# Throughhole_final_schematic.net
KiCad netlist of a schematic drawn in Altium Designer
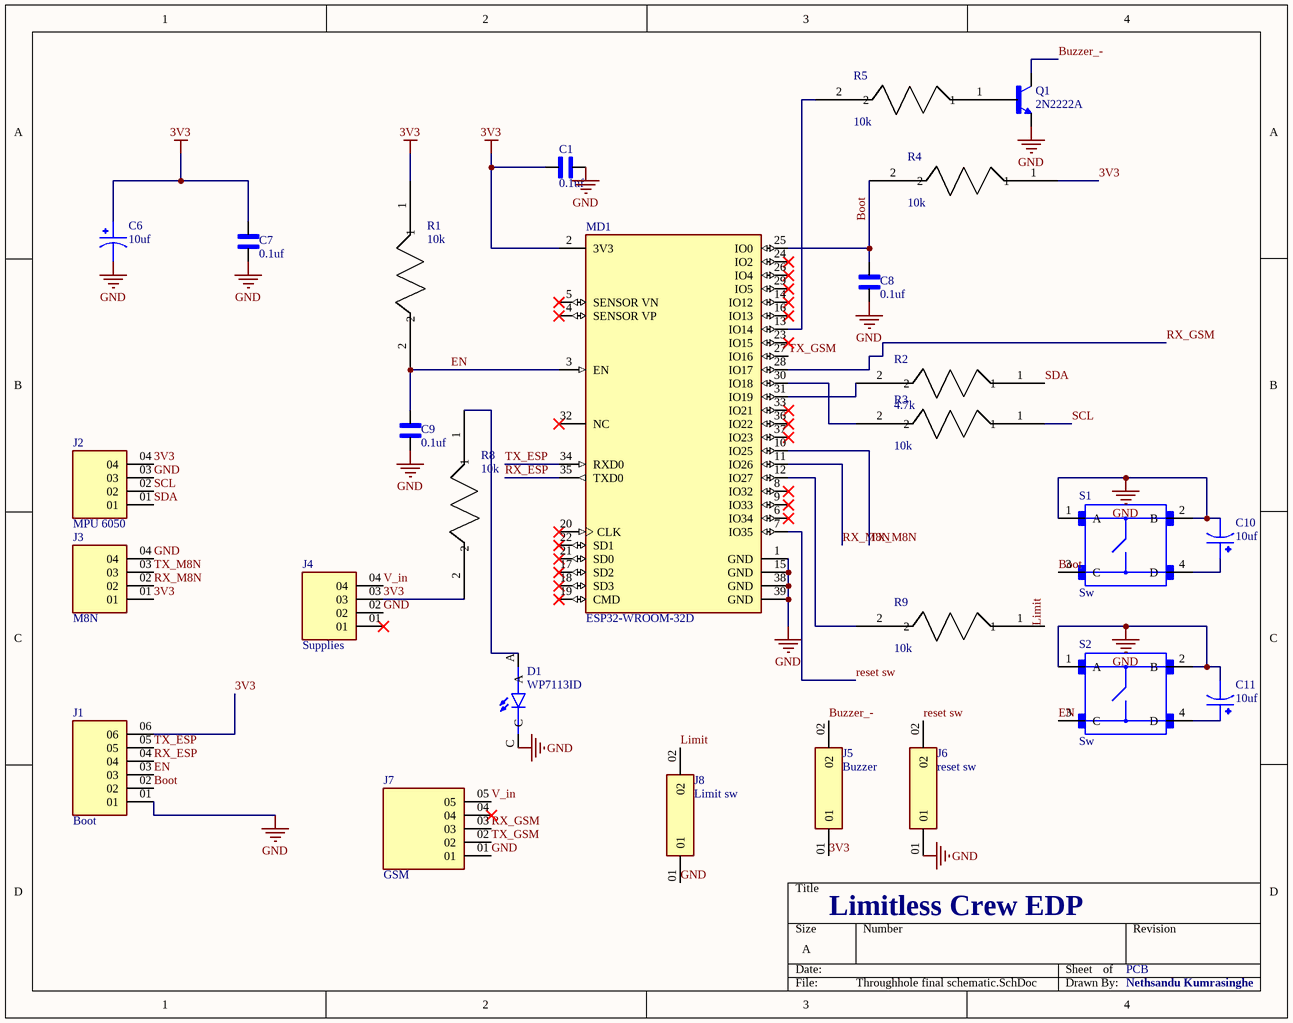
[diagram p0: Throughhole final schematic.SchDoc]

(export (version "E")
  (design (tool "Eeschema 10.0.6"))
  (components
    (comp (ref "C1")
      (value "0.1uf")
      (footprint "CAPRB500W50L450T250H550")
      (description "CAP CER 0.1UF 100V X7R RADIAL")
      (fields (field (name "MF") "TDK") (field (name "MP") "FK24X7R2A104KN000"))
      (libsource (lib "") (part "0.1uf_1"))
    )
    (comp (ref "C6")
      (value "10uf")
      (footprint "CAPPRD500W60D1000H2200")
      (description "CAP ALUM 10UF 20% 350V RADIAL")
      (fields (field (name "MF") "EPCOS") (field (name "MP") "B43890A4106M000"))
      (libsource (lib "") (part "10uf_1"))
    )
    (comp (ref "C7")
      (value "0.1uf")
      (footprint "CAPRB500W50L450T250H550")
      (description "CAP CER 0.1UF 100V X7R RADIAL")
      (fields (field (name "MF") "TDK") (field (name "MP") "FK24X7R2A104KN000"))
      (libsource (lib "") (part "0.1uf_2"))
    )
    (comp (ref "C8")
      (value "0.1uf")
      (footprint "CAPRB500W50L450T250H550")
      (description "CAP CER 0.1UF 100V X7R RADIAL")
      (fields (field (name "MF") "TDK") (field (name "MP") "FK24X7R2A104KN000"))
      (libsource (lib "Integrated_Library_final") (part "0.1uf"))
    )
    (comp (ref "C9")
      (value "0.1uf")
      (footprint "CAPRB500W50L450T250H550")
      (description "CAP CER 0.1UF 100V X7R RADIAL")
      (fields (field (name "MF") "TDK") (field (name "MP") "FK24X7R2A104KN000"))
      (libsource (lib "") (part "0.1uf_2"))
    )
    (comp (ref "C10")
      (value "10uf")
      (footprint "CAPPRD500W60D1000H2200")
      (description "CAP ALUM 10UF 20% 350V RADIAL")
      (fields (field (name "MF") "EPCOS") (field (name "MP") "B43890A4106M000"))
      (libsource (lib "Integrated_Library_final") (part "10uf"))
    )
    (comp (ref "C11")
      (value "10uf")
      (footprint "CAPPRD500W60D1000H2200")
      (description "CAP ALUM 10UF 20% 350V RADIAL")
      (fields (field (name "MF") "EPCOS") (field (name "MP") "B43890A4106M000"))
      (libsource (lib "Integrated_Library_final") (part "10uf"))
    )
    (comp (ref "D1")
      (value "WP7113ID")
      (footprint "LED_WP7113ID")
      (description "Red 617nm LED Indication - Discrete 2V Radial")
      (fields (field (name "MF") "Kingbright"))
      (libsource (lib "WP7113ID") (part "WP7113ID"))
    )
    (comp (ref "J1")
      (value "Boot")
      (footprint "SAMTEC_HMTSW-106-X-X-S-X")
      (description ".100 High-Temp Variable Post Height Terminal Strip")
      (fields (field (name "MF") "SAMTEC") (field (name "MP") "HMTSW-106-07-T-S-200"))
      (libsource (lib "Integrated_Library_final") (part "connector"))
    )
    (comp (ref "J2")
      (value "MPU 6050")
      (footprint "SAMTEC_MTLW-104-X-X-S-X")
      (fields (field (name "MF") "{'manufacturer': u'Samtec Inc.'}") (field (name "MP") "MTLW-104-X-X-S-X"))
      (libsource (lib "MTLW-104-X-X-S-X") (part "MTLW-104-X-X-S-X"))
    )
    (comp (ref "J3")
      (value "M8N")
      (footprint "SAMTEC_MTLW-104-X-X-S-X")
      (fields (field (name "MF") "{'manufacturer': u'Samtec Inc.'}") (field (name "MP") "MTLW-104-X-X-S-X"))
      (libsource (lib "MTLW-104-X-X-S-X") (part "MTLW-104-X-X-S-X"))
    )
    (comp (ref "J4")
      (value "Supplies")
      (footprint "SAMTEC_MTLW-104-X-X-S-X")
      (fields (field (name "MF") "{'manufacturer': u'Samtec Inc.'}") (field (name "MP") "MTLW-104-X-X-S-X"))
      (libsource (lib "MTLW-104-X-X-S-X") (part "MTLW-104-X-X-S-X"))
    )
    (comp (ref "J5")
      (value "Buzzer")
      (footprint "SAMTEC_MTSW-101-X-X-D-X")
      (description "Variable Height PCB Header Strips, 0.100 pitch")
      (fields (field (name "MF") "SAMTEC") (field (name "MP") "MTSW-101-09-L-D-210"))
      (libsource (lib "MTSW-101-X-X-D-X") (part "MTSW-101-X-X-D-X"))
    )
    (comp (ref "J6")
      (value "reset sw")
      (footprint "SAMTEC_MTSW-101-X-X-D-X")
      (description "Variable Height PCB Header Strips, 0.100 pitch")
      (fields (field (name "MF") "SAMTEC") (field (name "MP") "MTSW-101-09-L-D-210"))
      (libsource (lib "MTSW-101-X-X-D-X") (part "MTSW-101-X-X-D-X"))
    )
    (comp (ref "J7")
      (value "GSM")
      (footprint "SAMTEC_MTLW-105-06-T-S-135")
      (fields (field (name "MP") "MTLW-105-06-T-S-135"))
      (libsource (lib "MTLW-105-06-T-S-135") (part "MTLW-105-06-T-S-135"))
    )
    (comp (ref "J8")
      (value "Limit sw")
      (footprint "SAMTEC_MTSW-101-X-X-D-X")
      (description "Variable Height PCB Header Strips, 0.100 pitch")
      (fields (field (name "MF") "SAMTEC") (field (name "MP") "MTSW-101-09-L-D-210"))
      (libsource (lib "MTSW-101-X-X-D-X") (part "MTSW-101-X-X-D-X"))
    )
    (comp (ref "MD1")
      (value "ESP32-WROOM-32D")
      (footprint "FP-ESP32-WROOM-32D-MFG")
      (description "WIFI MODULE 32MBITS SPI FLASH")
      (fields
        (field (name "OCTOPART") "https://octopart.com/esp32-wroom-32d-espressif+systems-91040050")
        (field (name "MANUFACTURER") "Espressif Systems")
      )
      (libsource (lib "Integrated_Library_final") (part "esp32wroom32d"))
    )
    (comp (ref "Q1")
      (value "2N2222A")
      (footprint "TO92254P470H750-3")
      (description "BJT, TO-92, 40V, 600mA, NPN, 0.625W, 150Â°C")
      (fields (field (name "MF") "Diotec Semiconductor"))
      (libsource (lib "2N2222A") (part "2N2222A"))
    )
    (comp (ref "R1")
      (value "10k")
      (footprint "RESAD1100W55L680D260")
      (description "Fixed Resistor, Carbon Film, 0.25W, 10000ohm, 250V, 5% +/-Tol, -500,350ppm/Cel, Through Hole Mount")
      (fields
        (field (name "MANUFACTURER") "Yageo")
        (field (name "MANUFACTURER PART NUMBER") "CFR-25JR-52-10K")
      )
      (libsource (lib "Integrated_Library_final") (part "10k"))
    )
    (comp (ref "R2")
      (value "4.7k")
      (footprint "RESAD1100W55L680D260")
      (description "Fixed Resistor, Carbon Film, 0.25W, 4700ohm, 250V, 5% +/-Tol, -500,350ppm/Cel, Through Hole Mount")
      (fields
        (field (name "MANUFACTURER") "Yageo")
        (field (name "MANUFACTURER PART NUMBER") "CFR-25JR-52-4K7")
      )
      (libsource (lib "Integrated_Library_final") (part "4.7k"))
    )
    (comp (ref "R3")
      (value "10k")
      (footprint "RESAD1100W55L680D260")
      (description "Fixed Resistor, Carbon Film, 0.25W, 10000ohm, 250V, 5% +/-Tol, -500,350ppm/Cel, Through Hole Mount")
      (fields
        (field (name "MANUFACTURER") "Yageo")
        (field (name "MANUFACTURER PART NUMBER") "CFR-25JR-52-10K")
      )
      (libsource (lib "Integrated_Library_final") (part "10k"))
    )
    (comp (ref "R4")
      (value "10k")
      (footprint "RESAD1100W55L680D260")
      (description "Fixed Resistor, Carbon Film, 0.25W, 10000ohm, 250V, 5% +/-Tol, -500,350ppm/Cel, Through Hole Mount")
      (fields
        (field (name "MANUFACTURER") "Yageo")
        (field (name "MANUFACTURER PART NUMBER") "CFR-25JR-52-10K")
      )
      (libsource (lib "Integrated_Library_final") (part "10k"))
    )
    (comp (ref "R5")
      (value "10k")
      (footprint "RESAD1100W55L680D260")
      (description "Fixed Resistor, Carbon Film, 0.25W, 10000ohm, 250V, 5% +/-Tol, -500,350ppm/Cel, Through Hole Mount")
      (fields
        (field (name "MANUFACTURER") "Yageo")
        (field (name "MANUFACTURER PART NUMBER") "CFR-25JR-52-10K")
      )
      (libsource (lib "Integrated_Library_final") (part "10k"))
    )
    (comp (ref "R8")
      (value "10k")
      (footprint "RESAD1100W55L680D260")
      (description "Fixed Resistor, Carbon Film, 0.25W, 10000ohm, 250V, 5% +/-Tol, -500,350ppm/Cel, Through Hole Mount")
      (fields
        (field (name "MANUFACTURER") "Yageo")
        (field (name "MANUFACTURER PART NUMBER") "CFR-25JR-52-10K")
      )
      (libsource (lib "Integrated_Library_final") (part "10k"))
    )
    (comp (ref "R9")
      (value "10k")
      (footprint "RESAD1100W55L680D260")
      (description "Fixed Resistor, Carbon Film, 0.25W, 10000ohm, 250V, 5% +/-Tol, -500,350ppm/Cel, Through Hole Mount")
      (fields
        (field (name "MANUFACTURER") "Yageo")
        (field (name "MANUFACTURER PART NUMBER") "CFR-25JR-52-10K")
      )
      (libsource (lib "Integrated_Library_final") (part "10k"))
    )
    (comp (ref "S1")
      (value "Sw")
      (footprint "SW_TS-1109")
      (description "Heat Sink Full Brick DC/DC Converter Aluminum Top Mount")
      (fields (field (name "MP") "TS-1109") (field (name "MF") "Samtec Inc."))
      (libsource (lib "Integrated_Library_final") (part "Sw"))
    )
    (comp (ref "S2")
      (value "Sw")
      (footprint "SW_TS-1109")
      (description "Heat Sink Full Brick DC/DC Converter Aluminum Top Mount")
      (fields (field (name "MP") "TS-1109") (field (name "MF") "Samtec Inc."))
      (libsource (lib "Integrated_Library_final") (part "Sw"))
    )
  )
  (nets
    (net (code "1") (name "/Boot") (class "Default")
      (node (ref "C8") (pin "1") (pinfunction "1_1") (pintype "passive"))
      (node (ref "J1") (pin "02") (pinfunction "02_02") (pintype "passive"))
      (node (ref "MD1") (pin "25") (pinfunction "IO0_25") (pintype "bidirectional"))
      (node (ref "R4") (pin "2") (pinfunction "2_2") (pintype "passive"))
      (node (ref "S1") (pin "3") (pinfunction "C_3") (pintype "passive"))
    )
    (net (code "2") (name "/Buzzer_-") (class "Default")
      (node (ref "J5") (pin "02") (pinfunction "02_02") (pintype "passive"))
      (node (ref "Q1") (pin "3") (pinfunction "C_3") (pintype "passive"))
    )
    (net (code "3") (name "/EN") (class "Default")
      (node (ref "C9") (pin "2") (pinfunction "2_2") (pintype "passive"))
      (node (ref "J1") (pin "03") (pinfunction "03_03") (pintype "passive"))
      (node (ref "MD1") (pin "3") (pinfunction "EN_3") (pintype "input"))
      (node (ref "R1") (pin "2") (pinfunction "2_2") (pintype "passive"))
      (node (ref "S2") (pin "3") (pinfunction "C_3") (pintype "passive"))
    )
    (net (code "4") (name "/Limit") (class "Default")
      (node (ref "J8") (pin "02") (pinfunction "02_02") (pintype "passive"))
      (node (ref "R9") (pin "1") (pinfunction "1_1") (pintype "passive"))
    )
    (net (code "5") (name "/RX_ESP") (class "Default")
      (node (ref "J1") (pin "04") (pinfunction "04_04") (pintype "passive"))
      (node (ref "MD1") (pin "35") (pinfunction "TXD0_35") (pintype "output"))
    )
    (net (code "6") (name "/RX_GSM") (class "Default")
      (node (ref "J7") (pin "03") (pinfunction "03_03") (pintype "passive"))
      (node (ref "MD1") (pin "28") (pinfunction "IO17_28") (pintype "bidirectional"))
    )
    (net (code "7") (name "/RX_M8N") (class "Default")
      (node (ref "J3") (pin "02") (pinfunction "02_02") (pintype "passive"))
      (node (ref "MD1") (pin "11") (pinfunction "IO26_11") (pintype "bidirectional"))
    )
    (net (code "8") (name "/SCL") (class "Default")
      (node (ref "J2") (pin "02") (pinfunction "02_02") (pintype "passive"))
      (node (ref "R3") (pin "1") (pinfunction "1_1") (pintype "passive"))
    )
    (net (code "9") (name "/SDA") (class "Default")
      (node (ref "J2") (pin "01") (pinfunction "01_01") (pintype "passive"))
      (node (ref "R2") (pin "1") (pinfunction "1_1") (pintype "passive"))
    )
    (net (code "10") (name "/TX_ESP") (class "Default")
      (node (ref "J1") (pin "05") (pinfunction "05_05") (pintype "passive"))
      (node (ref "MD1") (pin "34") (pinfunction "RXD0_34") (pintype "input"))
    )
    (net (code "11") (name "/TX_GSM") (class "Default")
      (node (ref "J7") (pin "02") (pinfunction "02_02") (pintype "passive"))
      (node (ref "MD1") (pin "27") (pinfunction "IO16_27") (pintype "bidirectional"))
    )
    (net (code "12") (name "/TX_M8N") (class "Default")
      (node (ref "J3") (pin "03") (pinfunction "03_03") (pintype "passive"))
      (node (ref "MD1") (pin "10") (pinfunction "IO25_10") (pintype "bidirectional"))
    )
    (net (code "13") (name "/V_in") (class "Default")
      (node (ref "J4") (pin "04") (pinfunction "04_04") (pintype "passive"))
      (node (ref "J7") (pin "05") (pinfunction "05_05") (pintype "passive"))
    )
    (net (code "14") (name "/reset sw") (class "Default")
      (node (ref "J6") (pin "02") (pinfunction "02_02") (pintype "passive"))
      (node (ref "MD1") (pin "7") (pinfunction "IO35_7") (pintype "bidirectional"))
    )
    (net (code "15") (name "3V3") (class "Default")
      (node (ref "C1") (pin "1") (pinfunction "1_1") (pintype "passive"))
      (node (ref "C6") (pin "1") (pinfunction "1_1") (pintype "passive"))
      (node (ref "C7") (pin "2") (pinfunction "2_2") (pintype "passive"))
      (node (ref "J1") (pin "06") (pinfunction "06_06") (pintype "passive"))
      (node (ref "J2") (pin "04") (pinfunction "04_04") (pintype "passive"))
      (node (ref "J3") (pin "01") (pinfunction "01_01") (pintype "passive"))
      (node (ref "J4") (pin "03") (pinfunction "03_03") (pintype "passive"))
      (node (ref "J5") (pin "01") (pinfunction "01_01") (pintype "passive"))
      (node (ref "MD1") (pin "2") (pinfunction "3V3_2") (pintype "power_in"))
      (node (ref "R1") (pin "1") (pinfunction "1_1") (pintype "passive"))
      (node (ref "R4") (pin "1") (pinfunction "1_1") (pintype "passive"))
      (node (ref "R8") (pin "2") (pinfunction "2_2") (pintype "passive"))
    )
    (net (code "16") (name "GND") (class "Default")
      (node (ref "C1") (pin "2") (pinfunction "2_2") (pintype "passive"))
      (node (ref "C10") (pin "2") (pinfunction "2_2") (pintype "passive"))
      (node (ref "C11") (pin "2") (pinfunction "2_2") (pintype "passive"))
      (node (ref "C6") (pin "2") (pinfunction "2_2") (pintype "passive"))
      (node (ref "C7") (pin "1") (pinfunction "1_1") (pintype "passive"))
      (node (ref "C8") (pin "2") (pinfunction "2_2") (pintype "passive"))
      (node (ref "C9") (pin "1") (pinfunction "1_1") (pintype "passive"))
      (node (ref "D1") (pin "C") (pinfunction "C_C") (pintype "passive"))
      (node (ref "J1") (pin "01") (pinfunction "01_01") (pintype "passive"))
      (node (ref "J2") (pin "03") (pinfunction "03_03") (pintype "passive"))
      (node (ref "J3") (pin "04") (pinfunction "04_04") (pintype "passive"))
      (node (ref "J4") (pin "02") (pinfunction "02_02") (pintype "passive"))
      (node (ref "J6") (pin "01") (pinfunction "01_01") (pintype "passive"))
      (node (ref "J7") (pin "01") (pinfunction "01_01") (pintype "passive"))
      (node (ref "J8") (pin "01") (pinfunction "01_01") (pintype "passive"))
      (node (ref "MD1") (pin "1") (pinfunction "GND_1") (pintype "power_in"))
      (node (ref "MD1") (pin "15") (pinfunction "GND_15") (pintype "power_in"))
      (node (ref "MD1") (pin "38") (pinfunction "GND_38") (pintype "power_in"))
      (node (ref "MD1") (pin "39") (pinfunction "GND_39") (pintype "power_in"))
      (node (ref "Q1") (pin "1") (pinfunction "E_1") (pintype "passive"))
      (node (ref "S1") (pin "1") (pinfunction "A_1") (pintype "passive"))
      (node (ref "S1") (pin "2") (pinfunction "B_2") (pintype "passive"))
      (node (ref "S2") (pin "1") (pinfunction "A_1") (pintype "passive"))
      (node (ref "S2") (pin "2") (pinfunction "B_2") (pintype "passive"))
    )
    (net (code "17") (name "Net-(D1-PadA)") (class "Default")
      (node (ref "D1") (pin "A") (pinfunction "A_A") (pintype "passive"))
      (node (ref "R8") (pin "1") (pinfunction "1_1") (pintype "passive"))
    )
    (net (code "18") (name "Net-(MD1-IO14)") (class "Default")
      (node (ref "MD1") (pin "13") (pinfunction "IO14_13") (pintype "bidirectional"))
      (node (ref "R5") (pin "2") (pinfunction "2_2") (pintype "passive"))
    )
    (net (code "19") (name "Net-(MD1-IO18)") (class "Default")
      (node (ref "MD1") (pin "30") (pinfunction "IO18_30") (pintype "bidirectional"))
      (node (ref "R3") (pin "2") (pinfunction "2_2") (pintype "passive"))
    )
    (net (code "20") (name "Net-(MD1-IO19)") (class "Default")
      (node (ref "MD1") (pin "31") (pinfunction "IO19_31") (pintype "bidirectional"))
      (node (ref "R2") (pin "2") (pinfunction "2_2") (pintype "passive"))
    )
    (net (code "21") (name "Net-(MD1-IO27)") (class "Default")
      (node (ref "MD1") (pin "12") (pinfunction "IO27_12") (pintype "bidirectional"))
      (node (ref "R9") (pin "2") (pinfunction "2_2") (pintype "passive"))
    )
    (net (code "22") (name "Net-(Q1-B)") (class "Default")
      (node (ref "Q1") (pin "2") (pinfunction "B_2") (pintype "passive"))
      (node (ref "R5") (pin "1") (pinfunction "1_1") (pintype "passive"))
    )
    (net (code "23") (name "Net-(S1-D)") (class "Default")
      (node (ref "C10") (pin "1") (pinfunction "1_1") (pintype "passive"))
      (node (ref "S1") (pin "4") (pinfunction "D_4") (pintype "passive"))
    )
    (net (code "24") (name "Net-(S2-D)") (class "Default")
      (node (ref "C11") (pin "1") (pinfunction "1_1") (pintype "passive"))
      (node (ref "S2") (pin "4") (pinfunction "D_4") (pintype "passive"))
    )
    (net (code "25") (name "unconnected-(J4-Pad01)") (class "Default")
      (node (ref "J4") (pin "01") (pinfunction "01_01") (pintype "passive+no_connect"))
    )
    (net (code "26") (name "unconnected-(J7-Pad04)") (class "Default")
      (node (ref "J7") (pin "04") (pinfunction "04_04") (pintype "passive+no_connect"))
    )
    (net (code "27") (name "unconnected-(MD1-CLK-Pad20)") (class "Default")
      (node (ref "MD1") (pin "20") (pinfunction "CLK_20") (pintype "input+no_connect"))
    )
    (net (code "28") (name "unconnected-(MD1-CMD-Pad19)") (class "Default")
      (node (ref "MD1") (pin "19") (pinfunction "CMD_19") (pintype "bidirectional+no_connect"))
    )
    (net (code "29") (name "unconnected-(MD1-IO2-Pad24)") (class "Default")
      (node (ref "MD1") (pin "24") (pinfunction "IO2_24") (pintype "bidirectional+no_connect"))
    )
    (net (code "30") (name "unconnected-(MD1-IO4-Pad26)") (class "Default")
      (node (ref "MD1") (pin "26") (pinfunction "IO4_26") (pintype "bidirectional+no_connect"))
    )
    (net (code "31") (name "unconnected-(MD1-IO5-Pad29)") (class "Default")
      (node (ref "MD1") (pin "29") (pinfunction "IO5_29") (pintype "bidirectional+no_connect"))
    )
    (net (code "32") (name "unconnected-(MD1-IO12-Pad14)") (class "Default")
      (node (ref "MD1") (pin "14") (pinfunction "IO12_14") (pintype "bidirectional+no_connect"))
    )
    (net (code "33") (name "unconnected-(MD1-IO13-Pad16)") (class "Default")
      (node (ref "MD1") (pin "16") (pinfunction "IO13_16") (pintype "bidirectional+no_connect"))
    )
    (net (code "34") (name "unconnected-(MD1-IO15-Pad23)") (class "Default")
      (node (ref "MD1") (pin "23") (pinfunction "IO15_23") (pintype "bidirectional+no_connect"))
    )
    (net (code "35") (name "unconnected-(MD1-IO21-Pad33)") (class "Default")
      (node (ref "MD1") (pin "33") (pinfunction "IO21_33") (pintype "bidirectional+no_connect"))
    )
    (net (code "36") (name "unconnected-(MD1-IO22-Pad36)") (class "Default")
      (node (ref "MD1") (pin "36") (pinfunction "IO22_36") (pintype "bidirectional+no_connect"))
    )
    (net (code "37") (name "unconnected-(MD1-IO23-Pad37)") (class "Default")
      (node (ref "MD1") (pin "37") (pinfunction "IO23_37") (pintype "bidirectional+no_connect"))
    )
    (net (code "38") (name "unconnected-(MD1-IO32-Pad8)") (class "Default")
      (node (ref "MD1") (pin "8") (pinfunction "IO32_8") (pintype "bidirectional+no_connect"))
    )
    (net (code "39") (name "unconnected-(MD1-IO33-Pad9)") (class "Default")
      (node (ref "MD1") (pin "9") (pinfunction "IO33_9") (pintype "bidirectional+no_connect"))
    )
    (net (code "40") (name "unconnected-(MD1-IO34-Pad6)") (class "Default")
      (node (ref "MD1") (pin "6") (pinfunction "IO34_6") (pintype "bidirectional+no_connect"))
    )
    (net (code "41") (name "unconnected-(MD1-NC-Pad32)") (class "Default")
      (node (ref "MD1") (pin "32") (pinfunction "NC_32") (pintype "passive+no_connect"))
    )
    (net (code "42") (name "unconnected-(MD1-SD0-Pad21)") (class "Default")
      (node (ref "MD1") (pin "21") (pinfunction "SD0_21") (pintype "bidirectional+no_connect"))
    )
    (net (code "43") (name "unconnected-(MD1-SD1-Pad22)") (class "Default")
      (node (ref "MD1") (pin "22") (pinfunction "SD1_22") (pintype "bidirectional+no_connect"))
    )
    (net (code "44") (name "unconnected-(MD1-SD2-Pad17)") (class "Default")
      (node (ref "MD1") (pin "17") (pinfunction "SD2_17") (pintype "bidirectional+no_connect"))
    )
    (net (code "45") (name "unconnected-(MD1-SD3-Pad18)") (class "Default")
      (node (ref "MD1") (pin "18") (pinfunction "SD3_18") (pintype "bidirectional+no_connect"))
    )
    (net (code "46") (name "unconnected-(MD1-SENSOR_VN-Pad5)") (class "Default")
      (node (ref "MD1") (pin "5") (pinfunction "SENSOR_VN_5") (pintype "bidirectional+no_connect"))
    )
    (net (code "47") (name "unconnected-(MD1-SENSOR_VP-Pad4)") (class "Default")
      (node (ref "MD1") (pin "4") (pinfunction "SENSOR_VP_4") (pintype "bidirectional+no_connect"))
    )
  )
)
